# Ethernet.net
KiCad netlist of a schematic drawn in Altium Designer
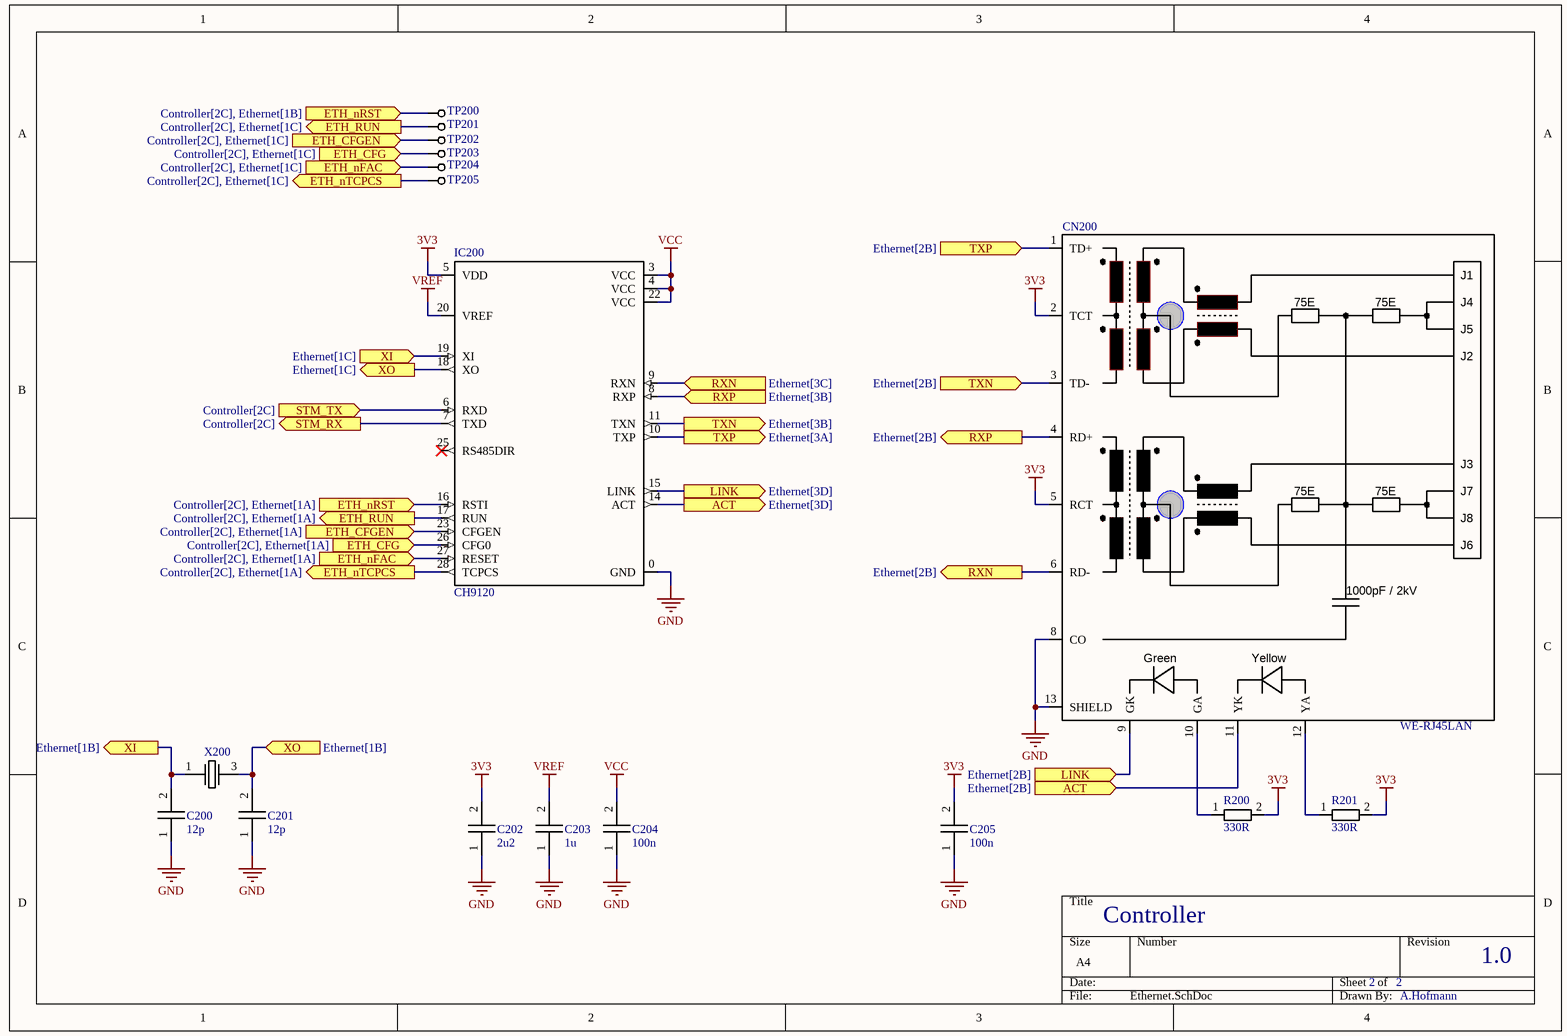
[diagram p0: Ethernet.SchDoc]

(export (version "E")
  (design (tool "Eeschema 10.0.6"))
  (components
    (comp (ref "C200") (value "12p") (footprint "C_0402") (libsource (lib "wol") (part "CeCa")))
    (comp (ref "C201") (value "12p") (footprint "C_0402") (libsource (lib "wol") (part "CeCa")))
    (comp (ref "C202") (value "2u2") (footprint "C_0603") (libsource (lib "wol") (part "CeCa")))
    (comp (ref "C203") (value "1u") (footprint "C_0603") (libsource (lib "wol") (part "CeCa")))
    (comp (ref "C204") (value "100n") (footprint "C_0402") (libsource (lib "wol") (part "CeCa")))
    (comp (ref "C205") (value "100n") (footprint "C_0402") (libsource (lib "wol") (part "CeCa")))
    (comp (ref "CN200")
      (value "WE-RJ45LAN")
      (footprint "7499010121A")
      (description "Modulare Steckverbinder / Ethernet-Steckverbinder WE-RJ45 Intgtd XFMR 1x1 THT Tab Up")
      (libsource (lib "wol") (part "WE-RJ45LAN"))
    )
    (comp (ref "IC200")
      (value "CH9120")
      (footprint "QFN28")
      (description "Network and UART Transparent Transmission Chip")
      (libsource (lib "wol") (part "CH9120"))
    )
    (comp (ref "R200") (value "330R") (footprint "R_0402") (libsource (lib "wol") (part "Res")))
    (comp (ref "R201") (value "330R") (footprint "R_0402") (libsource (lib "wol") (part "Res")))
    (comp (ref "TP200") (value "TP") (footprint "STP_0.5mm") (libsource (lib "wol") (part "TP")))
    (comp (ref "TP201") (value "TP") (footprint "STP_0.5mm") (libsource (lib "wol") (part "TP")))
    (comp (ref "TP202") (value "TP") (footprint "STP_0.5mm") (libsource (lib "wol") (part "TP")))
    (comp (ref "TP203") (value "TP") (footprint "STP_0.5mm") (libsource (lib "wol") (part "TP")))
    (comp (ref "TP204") (value "TP") (footprint "STP_0.5mm") (libsource (lib "wol") (part "TP")))
    (comp (ref "TP205") (value "TP") (footprint "STP_0.5mm") (libsource (lib "wol") (part "TP")))
    (comp (ref "X200")
      (value "XRCGB32M000F0L00R0")
      (footprint "HCR2016")
      (libsource (lib "wol") (part "XRCGB32M000F0L00R0"))
    )
  )
  (nets
    (net (code "1") (name "/ACT") (class "Default")
      (node (ref "CN200") (pin "11") (pinfunction "YK_11") (pintype "passive"))
      (node (ref "IC200") (pin "14") (pinfunction "ACT_14") (pintype "output"))
    )
    (net (code "2") (name "/ETH_CFG") (class "Default")
      (node (ref "IC200") (pin "26") (pinfunction "CFG0_26") (pintype "input"))
      (node (ref "TP203") (pin "1") (pintype "passive"))
    )
    (net (code "3") (name "/ETH_CFGEN") (class "Default")
      (node (ref "IC200") (pin "23") (pinfunction "CFGEN_23") (pintype "input"))
      (node (ref "TP202") (pin "1") (pintype "passive"))
    )
    (net (code "4") (name "/ETH_RUN") (class "Default")
      (node (ref "IC200") (pin "17") (pinfunction "RUN_17") (pintype "output"))
      (node (ref "TP201") (pin "1") (pintype "passive"))
    )
    (net (code "5") (name "/ETH_nFAC") (class "Default")
      (node (ref "IC200") (pin "27") (pinfunction "RESET_27") (pintype "input"))
      (node (ref "TP204") (pin "1") (pintype "passive"))
    )
    (net (code "6") (name "/ETH_nRST") (class "Default")
      (node (ref "IC200") (pin "16") (pinfunction "RSTI_16") (pintype "input"))
      (node (ref "TP200") (pin "1") (pintype "passive"))
    )
    (net (code "7") (name "/ETH_nTCPCS") (class "Default")
      (node (ref "IC200") (pin "28") (pinfunction "TCPCS_28") (pintype "output"))
      (node (ref "TP205") (pin "1") (pintype "passive"))
    )
    (net (code "8") (name "/LINK") (class "Default")
      (node (ref "CN200") (pin "9") (pinfunction "GK_9") (pintype "passive"))
      (node (ref "IC200") (pin "15") (pinfunction "LINK_15") (pintype "output"))
    )
    (net (code "9") (name "/RXN") (class "Default")
      (node (ref "CN200") (pin "6") (pinfunction "RD-_6") (pintype "passive"))
      (node (ref "IC200") (pin "9") (pinfunction "RXN_9") (pintype "input"))
    )
    (net (code "10") (name "/RXP") (class "Default")
      (node (ref "CN200") (pin "4") (pinfunction "RD+_4") (pintype "passive"))
      (node (ref "IC200") (pin "8") (pinfunction "RXP_8") (pintype "input"))
    )
    (net (code "11") (name "/STM_RX") (class "Default")
      (node (ref "IC200") (pin "7") (pinfunction "TXD_7") (pintype "output"))
    )
    (net (code "12") (name "/STM_TX") (class "Default")
      (node (ref "IC200") (pin "6") (pinfunction "RXD_6") (pintype "input"))
    )
    (net (code "13") (name "/TXN") (class "Default")
      (node (ref "CN200") (pin "3") (pinfunction "TD-_3") (pintype "passive"))
      (node (ref "IC200") (pin "11") (pinfunction "TXN_11") (pintype "output"))
    )
    (net (code "14") (name "/TXP") (class "Default")
      (node (ref "CN200") (pin "1") (pinfunction "TD+_1") (pintype "passive"))
      (node (ref "IC200") (pin "10") (pinfunction "TXP_10") (pintype "output"))
    )
    (net (code "15") (name "/XI") (class "Default")
      (node (ref "C200") (pin "2") (pintype "passive"))
      (node (ref "IC200") (pin "19") (pinfunction "XI_19") (pintype "input"))
      (node (ref "X200") (pin "1") (pintype "passive"))
    )
    (net (code "16") (name "/XO") (class "Default")
      (node (ref "C201") (pin "2") (pintype "passive"))
      (node (ref "IC200") (pin "18") (pinfunction "XO_18") (pintype "output"))
      (node (ref "X200") (pin "3") (pintype "passive"))
    )
    (net (code "17") (name "3V3") (class "Default")
      (node (ref "C202") (pin "2") (pintype "passive"))
      (node (ref "C205") (pin "2") (pintype "passive"))
      (node (ref "CN200") (pin "2") (pinfunction "TCT_2") (pintype "passive"))
      (node (ref "CN200") (pin "5") (pinfunction "RCT_5") (pintype "passive"))
      (node (ref "IC200") (pin "5") (pinfunction "VDD_5") (pintype "power_in"))
      (node (ref "R200") (pin "2") (pintype "passive"))
      (node (ref "R201") (pin "2") (pintype "passive"))
    )
    (net (code "18") (name "GND") (class "Default")
      (node (ref "C200") (pin "1") (pintype "passive"))
      (node (ref "C201") (pin "1") (pintype "passive"))
      (node (ref "C202") (pin "1") (pintype "passive"))
      (node (ref "C203") (pin "1") (pintype "passive"))
      (node (ref "C204") (pin "1") (pintype "passive"))
      (node (ref "C205") (pin "1") (pintype "passive"))
      (node (ref "CN200") (pin "13") (pinfunction "SHIELD_13") (pintype "passive"))
      (node (ref "CN200") (pin "8") (pinfunction "CO_8") (pintype "passive"))
      (node (ref "IC200") (pin "0") (pinfunction "GND_0") (pintype "power_in"))
    )
    (net (code "19") (name "Net-(CN200-GA)") (class "Default")
      (node (ref "CN200") (pin "10") (pinfunction "GA_10") (pintype "passive"))
      (node (ref "R200") (pin "1") (pintype "passive"))
    )
    (net (code "20") (name "Net-(CN200-YA)") (class "Default")
      (node (ref "CN200") (pin "12") (pinfunction "YA_12") (pintype "passive"))
      (node (ref "R201") (pin "1") (pintype "passive"))
    )
    (net (code "21") (name "VCC") (class "Default")
      (node (ref "C204") (pin "2") (pintype "passive"))
      (node (ref "IC200") (pin "22") (pinfunction "VCC_22") (pintype "power_in"))
      (node (ref "IC200") (pin "3") (pinfunction "VCC_3") (pintype "power_in"))
      (node (ref "IC200") (pin "4") (pinfunction "VCC_4") (pintype "power_in"))
    )
    (net (code "22") (name "VREF") (class "Default")
      (node (ref "C203") (pin "2") (pintype "passive"))
      (node (ref "IC200") (pin "20") (pinfunction "VREF_20") (pintype "power_in"))
    )
    (net (code "23") (name "unconnected-(IC200-RS485DIR-Pad25)") (class "Default")
      (node (ref "IC200") (pin "25") (pinfunction "RS485DIR_25") (pintype "output+no_connect"))
    )
  )
)
